# power.net
KiCad netlist of a schematic drawn in EAGLE
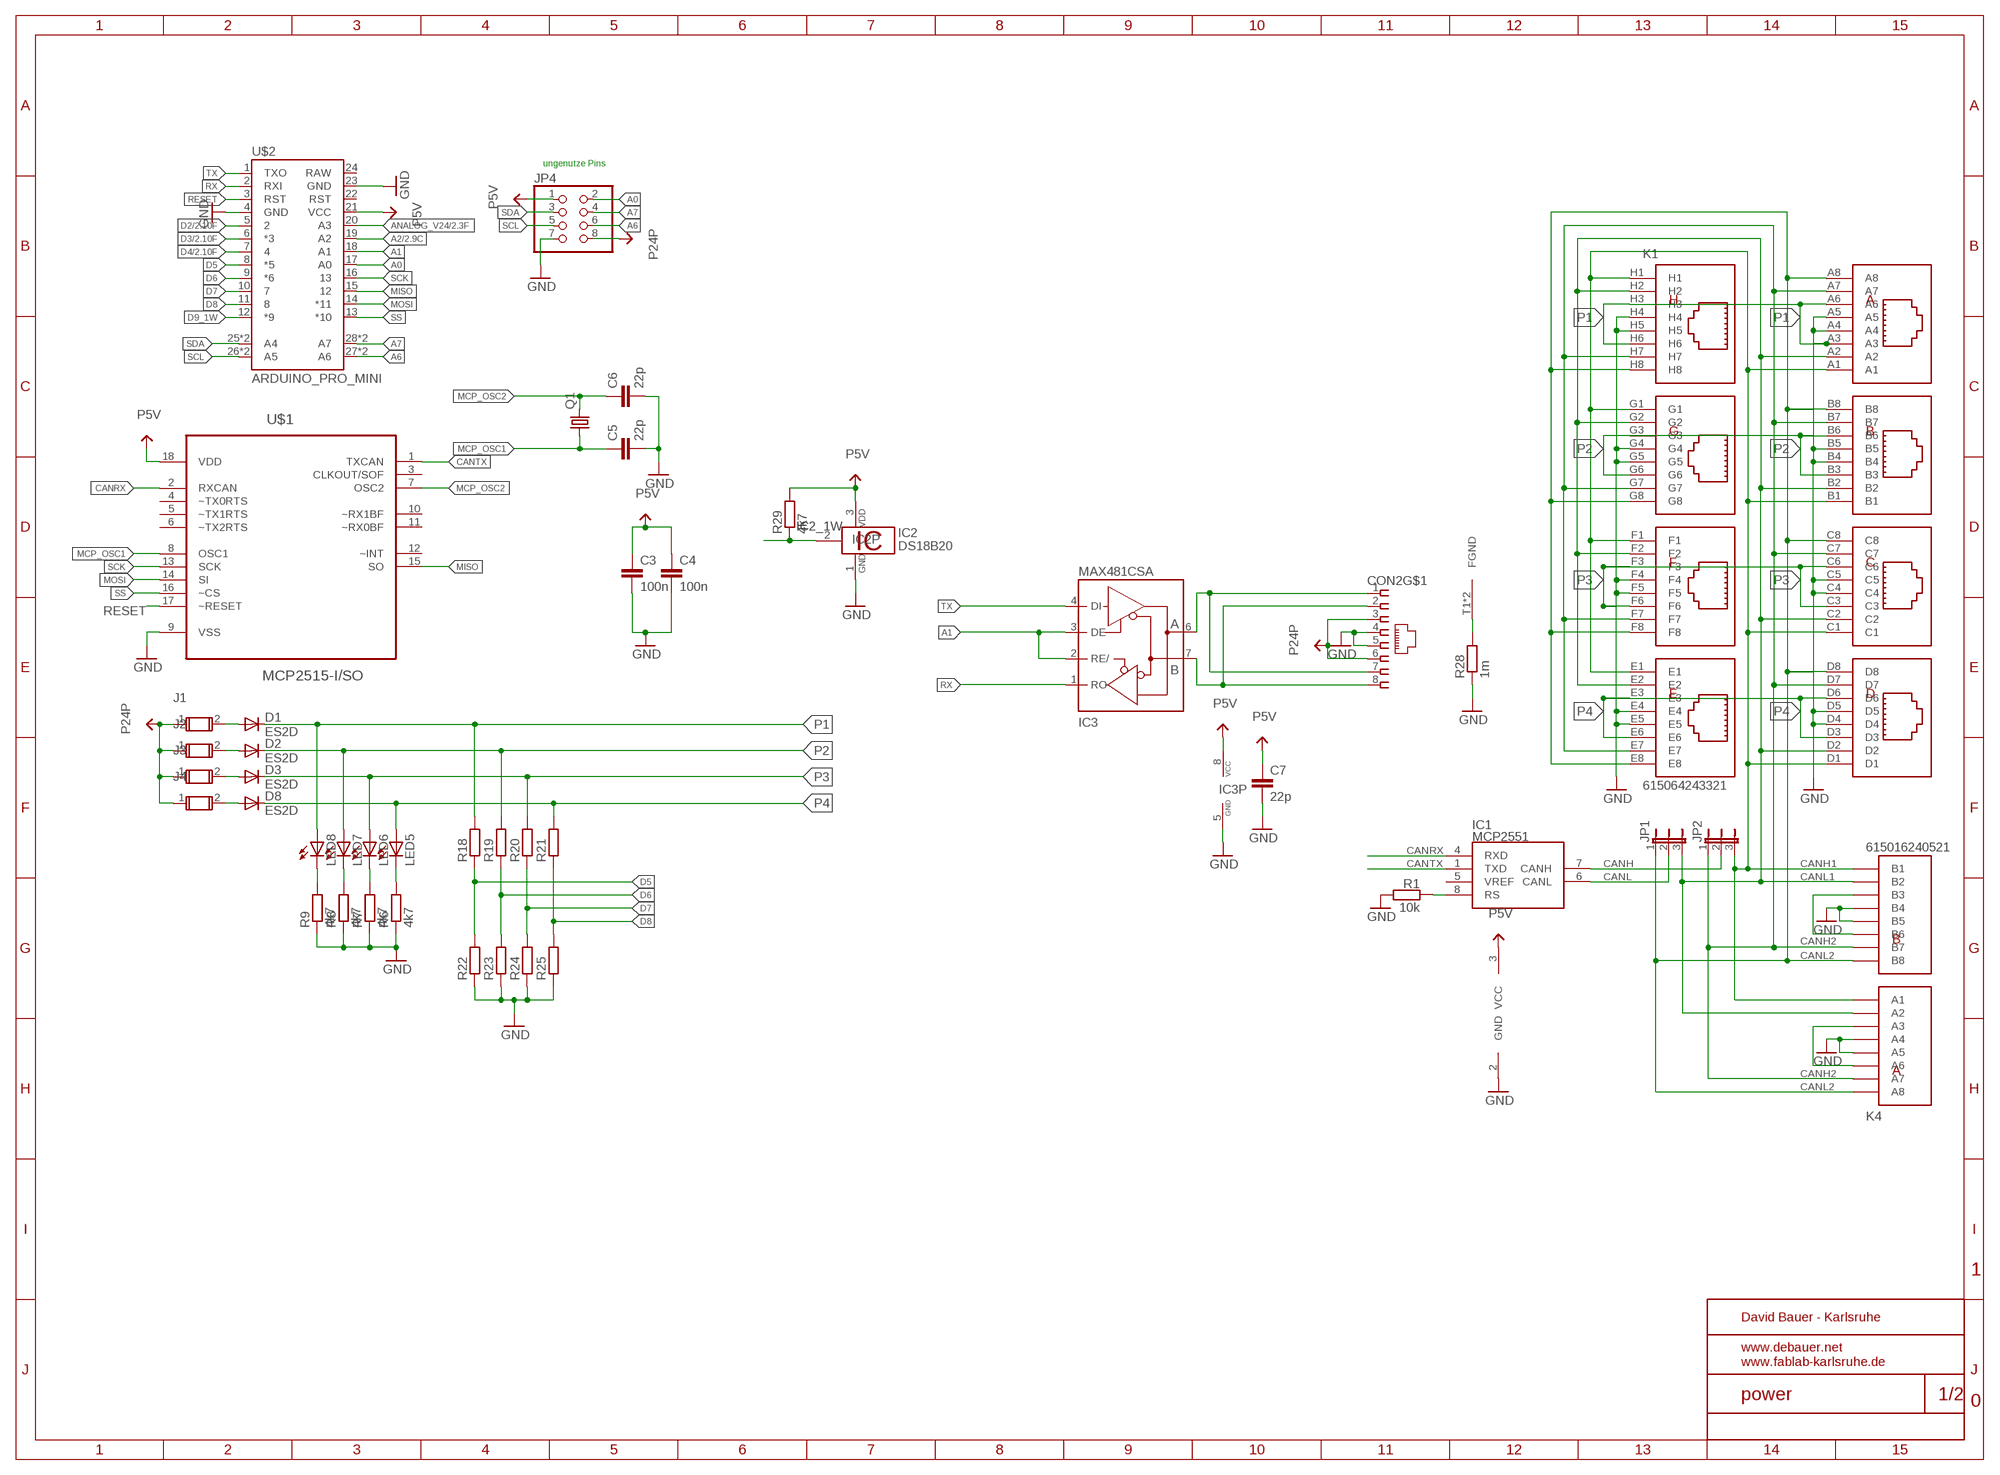
[diagram p0: schematic, sheet 1]
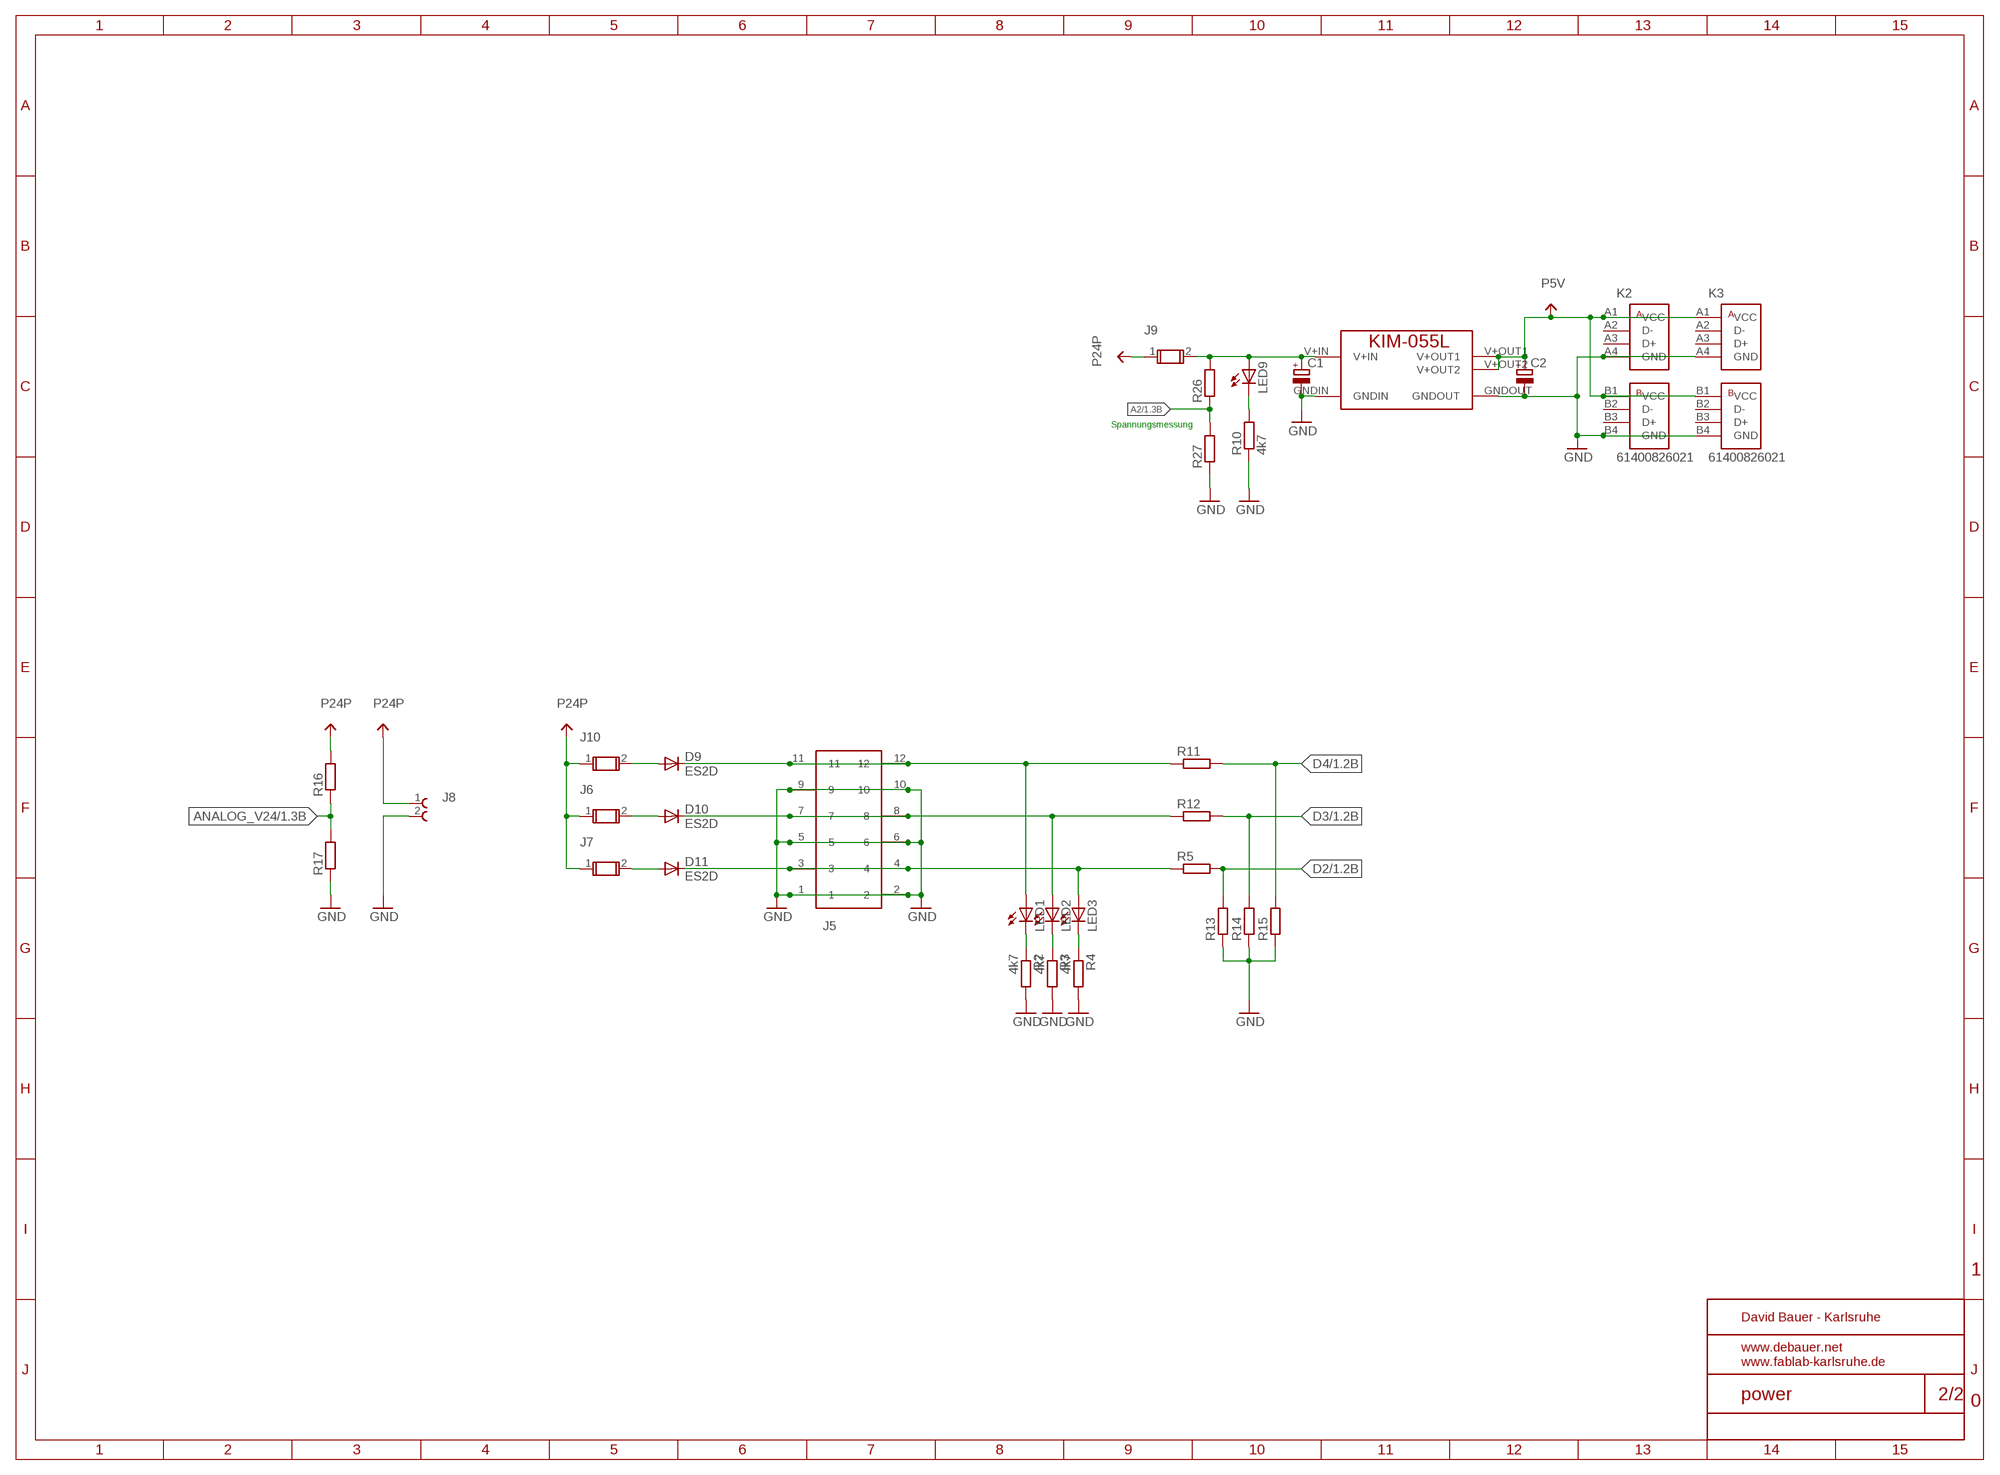
[diagram p1: schematic, sheet 2]

(export (version "E")
  (design (tool "Eeschema 10.0.6"))
  (components
    (comp (ref "C1")
      (value "CPOL-EUE5-10.5")
      (footprint "eagle-import:E5-10,5")
      (libsource (lib "eagle-import") (part "CPOL-EUE5-10.5"))
    )
    (comp (ref "C2")
      (value "CPOL-EUE5-10.5")
      (footprint "eagle-import:E5-10,5")
      (libsource (lib "eagle-import") (part "CPOL-EUE5-10.5"))
    )
    (comp (ref "D9")
      (value "ES2D")
      (footprint "eagle-import:SMB")
      (libsource (lib "eagle-import") (part "ES2D"))
    )
    (comp (ref "D10")
      (value "ES2D")
      (footprint "eagle-import:SMB")
      (libsource (lib "eagle-import") (part "ES2D"))
    )
    (comp (ref "D11")
      (value "ES2D")
      (footprint "eagle-import:SMB")
      (libsource (lib "eagle-import") (part "ES2D"))
    )
    (comp (ref "J5")
      (value "691332510012")
      (footprint "eagle-import:691332510012")
      (libsource (lib "eagle-import") (part "691332510012"))
    )
    (comp (ref "J6")
      (value "696101000002")
      (footprint "eagle-import:696101000002")
      (libsource (lib "eagle-import") (part "696101000002"))
    )
    (comp (ref "J7")
      (value "696101000002")
      (footprint "eagle-import:696101000002")
      (libsource (lib "eagle-import") (part "696101000002"))
    )
    (comp (ref "J8")
      (value "691312510002")
      (footprint "eagle-import:691312510002")
      (libsource (lib "eagle-import") (part "691312510002"))
    )
    (comp (ref "J9")
      (value "696101000002")
      (footprint "eagle-import:696101000002")
      (libsource (lib "eagle-import") (part "696101000002"))
    )
    (comp (ref "J10")
      (value "696101000002")
      (footprint "eagle-import:696101000002")
      (libsource (lib "eagle-import") (part "696101000002"))
    )
    (comp (ref "K2")
      (value "61400826021")
      (footprint "eagle-import:61400826021")
      (libsource (lib "eagle-import") (part "61400826021"))
    )
    (comp (ref "K3")
      (value "61400826021")
      (footprint "eagle-import:61400826021")
      (libsource (lib "eagle-import") (part "61400826021"))
    )
    (comp (ref "LED1")
      (value "LED3MM")
      (footprint "eagle-import:LED3MM")
      (libsource (lib "eagle-import") (part "LED3MM"))
    )
    (comp (ref "LED2")
      (value "LED3MM")
      (footprint "eagle-import:LED3MM")
      (libsource (lib "eagle-import") (part "LED3MM"))
    )
    (comp (ref "LED3")
      (value "LED3MM")
      (footprint "eagle-import:LED3MM")
      (libsource (lib "eagle-import") (part "LED3MM"))
    )
    (comp (ref "LED9")
      (value "LED3MM")
      (footprint "eagle-import:LED3MM")
      (libsource (lib "eagle-import") (part "LED3MM"))
    )
    (comp (ref "MOD1")
      (value "KIM-055L")
      (footprint "eagle-import:KIM-055L")
      (libsource (lib "eagle-import") (part "KIM-055L"))
    )
    (comp (ref "R2")
      (value "4k7")
      (footprint "eagle-import:R0805")
      (libsource (lib "eagle-import") (part "schlager_passiv_R-EU_R0805"))
    )
    (comp (ref "R3")
      (value "4k7")
      (footprint "eagle-import:R0805")
      (libsource (lib "eagle-import") (part "schlager_passiv_R-EU_R0805"))
    )
    (comp (ref "R4")
      (value "4k7")
      (footprint "eagle-import:R0805")
      (libsource (lib "eagle-import") (part "schlager_passiv_R-EU_R0805"))
    )
    (comp (ref "R5")
      (value "R-EU_R0805")
      (footprint "eagle-import:R0805")
      (libsource (lib "eagle-import") (part "schlager_passiv_R-EU_R0805"))
    )
    (comp (ref "R10")
      (value "4k7")
      (footprint "eagle-import:R0805")
      (libsource (lib "eagle-import") (part "schlager_passiv_R-EU_R0805"))
    )
    (comp (ref "R11")
      (value "R-EU_R0805")
      (footprint "eagle-import:R0805")
      (libsource (lib "eagle-import") (part "schlager_passiv_R-EU_R0805"))
    )
    (comp (ref "R12")
      (value "R-EU_R0805")
      (footprint "eagle-import:R0805")
      (libsource (lib "eagle-import") (part "schlager_passiv_R-EU_R0805"))
    )
    (comp (ref "R13")
      (value "R-EU_R0805")
      (footprint "eagle-import:R0805")
      (libsource (lib "eagle-import") (part "schlager_passiv_R-EU_R0805"))
    )
    (comp (ref "R14")
      (value "R-EU_R0805")
      (footprint "eagle-import:R0805")
      (libsource (lib "eagle-import") (part "schlager_passiv_R-EU_R0805"))
    )
    (comp (ref "R15")
      (value "R-EU_R0805")
      (footprint "eagle-import:R0805")
      (libsource (lib "eagle-import") (part "schlager_passiv_R-EU_R0805"))
    )
    (comp (ref "R16")
      (value "R-EU_R0805")
      (footprint "eagle-import:R0805")
      (libsource (lib "eagle-import") (part "schlager_passiv_R-EU_R0805"))
    )
    (comp (ref "R17")
      (value "R-EU_R0805")
      (footprint "eagle-import:R0805")
      (libsource (lib "eagle-import") (part "schlager_passiv_R-EU_R0805"))
    )
    (comp (ref "R26")
      (value "R-EU_R0805")
      (footprint "eagle-import:R0805")
      (libsource (lib "eagle-import") (part "schlager_passiv_R-EU_R0805"))
    )
    (comp (ref "R27")
      (value "R-EU_R0805")
      (footprint "eagle-import:R0805")
      (libsource (lib "eagle-import") (part "schlager_passiv_R-EU_R0805"))
    )
    (comp (ref "C3")
      (value "100n")
      (footprint "eagle-import:C0805")
      (libsource (lib "eagle-import") (part "C-EUC0805"))
    )
    (comp (ref "C4")
      (value "100n")
      (footprint "eagle-import:C0805")
      (libsource (lib "eagle-import") (part "C-EUC0805"))
    )
    (comp (ref "C5")
      (value "22p")
      (footprint "eagle-import:C0805")
      (libsource (lib "eagle-import") (part "C-EUC0805"))
    )
    (comp (ref "C6")
      (value "22p")
      (footprint "eagle-import:C0805")
      (libsource (lib "eagle-import") (part "C-EUC0805"))
    )
    (comp (ref "C7")
      (value "22p")
      (footprint "eagle-import:C0805")
      (libsource (lib "eagle-import") (part "C-EUC0805"))
    )
    (comp (ref "CON2")
      (value "MEBP_8-8G")
      (footprint "eagle-import:MEBP")
      (libsource (lib "eagle-import") (part "MEBP_8-8G"))
    )
    (comp (ref "D1")
      (value "ES2D")
      (footprint "eagle-import:SMB")
      (libsource (lib "eagle-import") (part "ES2D"))
    )
    (comp (ref "D2")
      (value "ES2D")
      (footprint "eagle-import:SMB")
      (libsource (lib "eagle-import") (part "ES2D"))
    )
    (comp (ref "D3")
      (value "ES2D")
      (footprint "eagle-import:SMB")
      (libsource (lib "eagle-import") (part "ES2D"))
    )
    (comp (ref "D8")
      (value "ES2D")
      (footprint "eagle-import:SMB")
      (libsource (lib "eagle-import") (part "ES2D"))
    )
    (comp (ref "IC1")
      (value "MCP2551")
      (footprint "eagle-import:SO-8")
      (libsource (lib "eagle-import") (part "MCP2551"))
    )
    (comp (ref "IC2")
      (value "DS18B20")
      (footprint "eagle-import:TO92-")
      (libsource (lib "eagle-import") (part "DS18B20"))
    )
    (comp (ref "IC3")
      (value "MAX481CSA")
      (footprint "eagle-import:SO08")
      (fields (field (name "MF") "MAXIM"))
      (libsource (lib "eagle-import") (part "MAX481CSA"))
    )
    (comp (ref "J1")
      (value "696101000002")
      (footprint "eagle-import:696101000002")
      (libsource (lib "eagle-import") (part "696101000002"))
    )
    (comp (ref "J2")
      (value "696101000002")
      (footprint "eagle-import:696101000002")
      (libsource (lib "eagle-import") (part "696101000002"))
    )
    (comp (ref "J3")
      (value "696101000002")
      (footprint "eagle-import:696101000002")
      (libsource (lib "eagle-import") (part "696101000002"))
    )
    (comp (ref "J4")
      (value "696101000002")
      (footprint "eagle-import:696101000002")
      (libsource (lib "eagle-import") (part "696101000002"))
    )
    (comp (ref "JP1")
      (value "JP2E")
      (footprint "eagle-import:JP2")
      (libsource (lib "eagle-import") (part "JP2E"))
    )
    (comp (ref "JP2")
      (value "JP2E")
      (footprint "eagle-import:JP2")
      (libsource (lib "eagle-import") (part "JP2E"))
    )
    (comp (ref "JP4")
      (value "PINHD-2X4")
      (footprint "eagle-import:2X04")
      (libsource (lib "eagle-import") (part "PINHD-2X4"))
    )
    (comp (ref "K1")
      (value "615064243321")
      (footprint "eagle-import:615064243321")
      (libsource (lib "eagle-import") (part "615064243321"))
    )
    (comp (ref "K4")
      (value "615016240521")
      (footprint "eagle-import:615016240521")
      (libsource (lib "eagle-import") (part "615016240521"))
    )
    (comp (ref "LED5")
      (value "LED3MM")
      (footprint "eagle-import:LED3MM")
      (libsource (lib "eagle-import") (part "LED3MM"))
    )
    (comp (ref "LED6")
      (value "LED3MM")
      (footprint "eagle-import:LED3MM")
      (libsource (lib "eagle-import") (part "LED3MM"))
    )
    (comp (ref "LED7")
      (value "LED3MM")
      (footprint "eagle-import:LED3MM")
      (libsource (lib "eagle-import") (part "LED3MM"))
    )
    (comp (ref "LED8")
      (value "LED3MM")
      (footprint "eagle-import:LED3MM")
      (libsource (lib "eagle-import") (part "LED3MM"))
    )
    (comp (ref "Q1")
      (value "CRYSTALHC49S")
      (footprint "eagle-import:HC49_S")
      (libsource (lib "eagle-import") (part "CRYSTALHC49S"))
    )
    (comp (ref "R1")
      (value "10k")
      (footprint "eagle-import:R0603")
      (libsource (lib "eagle-import") (part "R-EU_R0603"))
    )
    (comp (ref "R6")
      (value "4k7")
      (footprint "eagle-import:R0805")
      (libsource (lib "eagle-import") (part "schlager_passiv_R-EU_R0805"))
    )
    (comp (ref "R7")
      (value "4k7")
      (footprint "eagle-import:R0805")
      (libsource (lib "eagle-import") (part "schlager_passiv_R-EU_R0805"))
    )
    (comp (ref "R8")
      (value "4k7")
      (footprint "eagle-import:R0805")
      (libsource (lib "eagle-import") (part "schlager_passiv_R-EU_R0805"))
    )
    (comp (ref "R9")
      (value "4k7")
      (footprint "eagle-import:R0805")
      (libsource (lib "eagle-import") (part "schlager_passiv_R-EU_R0805"))
    )
    (comp (ref "R18")
      (value "R-EU_R0805")
      (footprint "eagle-import:R0805")
      (libsource (lib "eagle-import") (part "schlager_passiv_R-EU_R0805"))
    )
    (comp (ref "R19")
      (value "R-EU_R0805")
      (footprint "eagle-import:R0805")
      (libsource (lib "eagle-import") (part "schlager_passiv_R-EU_R0805"))
    )
    (comp (ref "R20")
      (value "R-EU_R0805")
      (footprint "eagle-import:R0805")
      (libsource (lib "eagle-import") (part "schlager_passiv_R-EU_R0805"))
    )
    (comp (ref "R21")
      (value "R-EU_R0805")
      (footprint "eagle-import:R0805")
      (libsource (lib "eagle-import") (part "schlager_passiv_R-EU_R0805"))
    )
    (comp (ref "R22")
      (value "R-EU_R0805")
      (footprint "eagle-import:R0805")
      (libsource (lib "eagle-import") (part "schlager_passiv_R-EU_R0805"))
    )
    (comp (ref "R23")
      (value "R-EU_R0805")
      (footprint "eagle-import:R0805")
      (libsource (lib "eagle-import") (part "schlager_passiv_R-EU_R0805"))
    )
    (comp (ref "R24")
      (value "R-EU_R0805")
      (footprint "eagle-import:R0805")
      (libsource (lib "eagle-import") (part "schlager_passiv_R-EU_R0805"))
    )
    (comp (ref "R25")
      (value "R-EU_R0805")
      (footprint "eagle-import:R0805")
      (libsource (lib "eagle-import") (part "schlager_passiv_R-EU_R0805"))
    )
    (comp (ref "R28")
      (value "1m")
      (footprint "eagle-import:R0805")
      (libsource (lib "eagle-import") (part "schlager_passiv_R-EU_R0805"))
    )
    (comp (ref "R29")
      (value "4k7")
      (footprint "eagle-import:R0805")
      (libsource (lib "eagle-import") (part "schlager_passiv_R-EU_R0805"))
    )
    (comp (ref "U$1")
      (value "MCP2515-I/SO")
      (footprint "eagle-import:SOIC127P1034X264-18N")
      (libsource (lib "eagle-import") (part "MCP2515-I/SO"))
    )
    (comp (ref "U$2")
      (value "ARDUINO_PRO_MINI")
      (footprint "eagle-import:ARDUINO_PRO_MINI")
      (libsource (lib "eagle-import") (part "ARDUINO_PRO_MINI"))
    )
  )
  (nets
    (net (code "1") (name "A0") (class "Default")
      (node (ref "JP4") (pin "2") (pinfunction "2_2") (pintype "passive"))
      (node (ref "U$2") (pin "17") (pinfunction "A0_17") (pintype "bidirectional"))
    )
    (net (code "2") (name "A1") (class "Default")
      (node (ref "IC3") (pin "2") (pinfunction "RE/_2") (pintype "input"))
      (node (ref "IC3") (pin "3") (pinfunction "DE_3") (pintype "input"))
      (node (ref "U$2") (pin "18") (pinfunction "A1_18") (pintype "bidirectional"))
    )
    (net (code "3") (name "A2") (class "Default")
      (node (ref "R26") (pin "1") (pinfunction "1_1") (pintype "passive"))
      (node (ref "R27") (pin "2") (pinfunction "2_2") (pintype "passive"))
      (node (ref "U$2") (pin "19") (pinfunction "A2_19") (pintype "bidirectional"))
    )
    (net (code "4") (name "A6") (class "Default")
      (node (ref "JP4") (pin "6") (pinfunction "6_6") (pintype "passive"))
      (node (ref "U$2") (pin "27") (pinfunction "A6_27") (pintype "bidirectional"))
      (node (ref "U$2") (pin "A6") (pinfunction "A6_A6") (pintype "bidirectional"))
    )
    (net (code "5") (name "A7") (class "Default")
      (node (ref "JP4") (pin "4") (pinfunction "4_4") (pintype "passive"))
      (node (ref "U$2") (pin "28") (pinfunction "A7_28") (pintype "bidirectional"))
      (node (ref "U$2") (pin "A7") (pinfunction "A7_A7") (pintype "bidirectional"))
    )
    (net (code "6") (name "ANALOG_V24") (class "Default")
      (node (ref "R16") (pin "1") (pinfunction "1_1") (pintype "passive"))
      (node (ref "R17") (pin "2") (pinfunction "2_2") (pintype "passive"))
      (node (ref "U$2") (pin "20") (pinfunction "A3_20") (pintype "bidirectional"))
    )
    (net (code "7") (name "CANH") (class "Default")
      (node (ref "IC1") (pin "7") (pinfunction "CANH_7") (pintype "bidirectional"))
      (node (ref "JP2") (pin "2") (pinfunction "2_2") (pintype "passive"))
    )
    (net (code "8") (name "CANH1") (class "Default")
      (node (ref "JP2") (pin "3") (pinfunction "3_3") (pintype "passive"))
      (node (ref "K1") (pin "A1") (pinfunction "A1_A1") (pintype "passive"))
      (node (ref "K1") (pin "B1") (pinfunction "B1_B1") (pintype "passive"))
      (node (ref "K1") (pin "C1") (pinfunction "C1_C1") (pintype "passive"))
      (node (ref "K1") (pin "D1") (pinfunction "D1_D1") (pintype "passive"))
      (node (ref "K1") (pin "E1") (pinfunction "E1_E1") (pintype "passive"))
      (node (ref "K1") (pin "F1") (pinfunction "F1_F1") (pintype "passive"))
      (node (ref "K1") (pin "G1") (pinfunction "G1_G1") (pintype "passive"))
      (node (ref "K1") (pin "H1") (pinfunction "H1_H1") (pintype "passive"))
      (node (ref "K4") (pin "A1") (pinfunction "A1_A1") (pintype "passive"))
      (node (ref "K4") (pin "B1") (pinfunction "B1_B1") (pintype "passive"))
    )
    (net (code "9") (name "CANH2") (class "Default")
      (node (ref "JP2") (pin "1") (pinfunction "1_1") (pintype "passive"))
      (node (ref "K1") (pin "A7") (pinfunction "A7_A7") (pintype "passive"))
      (node (ref "K1") (pin "B7") (pinfunction "B7_B7") (pintype "passive"))
      (node (ref "K1") (pin "C7") (pinfunction "C7_C7") (pintype "passive"))
      (node (ref "K1") (pin "D7") (pinfunction "D7_D7") (pintype "passive"))
      (node (ref "K1") (pin "E7") (pinfunction "E7_E7") (pintype "passive"))
      (node (ref "K1") (pin "F7") (pinfunction "F7_F7") (pintype "passive"))
      (node (ref "K1") (pin "G7") (pinfunction "G7_G7") (pintype "passive"))
      (node (ref "K1") (pin "H7") (pinfunction "H7_H7") (pintype "passive"))
      (node (ref "K4") (pin "A7") (pinfunction "A7_A7") (pintype "passive"))
      (node (ref "K4") (pin "B7") (pinfunction "B7_B7") (pintype "passive"))
    )
    (net (code "10") (name "CANL") (class "Default")
      (node (ref "IC1") (pin "6") (pinfunction "CANL_6") (pintype "bidirectional"))
      (node (ref "JP1") (pin "2") (pinfunction "2_2") (pintype "passive"))
    )
    (net (code "11") (name "CANL1") (class "Default")
      (node (ref "JP1") (pin "3") (pinfunction "3_3") (pintype "passive"))
      (node (ref "K1") (pin "A2") (pinfunction "A2_A2") (pintype "passive"))
      (node (ref "K1") (pin "B2") (pinfunction "B2_B2") (pintype "passive"))
      (node (ref "K1") (pin "C2") (pinfunction "C2_C2") (pintype "passive"))
      (node (ref "K1") (pin "D2") (pinfunction "D2_D2") (pintype "passive"))
      (node (ref "K1") (pin "E2") (pinfunction "E2_E2") (pintype "passive"))
      (node (ref "K1") (pin "F2") (pinfunction "F2_F2") (pintype "passive"))
      (node (ref "K1") (pin "G2") (pinfunction "G2_G2") (pintype "passive"))
      (node (ref "K1") (pin "H2") (pinfunction "H2_H2") (pintype "passive"))
      (node (ref "K4") (pin "A2") (pinfunction "A2_A2") (pintype "passive"))
      (node (ref "K4") (pin "B2") (pinfunction "B2_B2") (pintype "passive"))
    )
    (net (code "12") (name "CANL2") (class "Default")
      (node (ref "JP1") (pin "1") (pinfunction "1_1") (pintype "passive"))
      (node (ref "K1") (pin "A8") (pinfunction "A8_A8") (pintype "passive"))
      (node (ref "K1") (pin "B8") (pinfunction "B8_B8") (pintype "passive"))
      (node (ref "K1") (pin "C8") (pinfunction "C8_C8") (pintype "passive"))
      (node (ref "K1") (pin "D8") (pinfunction "D8_D8") (pintype "passive"))
      (node (ref "K1") (pin "E8") (pinfunction "E8_E8") (pintype "passive"))
      (node (ref "K1") (pin "F8") (pinfunction "F8_F8") (pintype "passive"))
      (node (ref "K1") (pin "G8") (pinfunction "G8_G8") (pintype "passive"))
      (node (ref "K1") (pin "H8") (pinfunction "H8_H8") (pintype "passive"))
      (node (ref "K4") (pin "A8") (pinfunction "A8_A8") (pintype "passive"))
      (node (ref "K4") (pin "B8") (pinfunction "B8_B8") (pintype "passive"))
    )
    (net (code "13") (name "CANRX") (class "Default")
      (node (ref "IC1") (pin "4") (pinfunction "RXD_4") (pintype "bidirectional"))
      (node (ref "U$1") (pin "2") (pinfunction "RXCAN_2") (pintype "input"))
    )
    (net (code "14") (name "CANTX") (class "Default")
      (node (ref "IC1") (pin "1") (pinfunction "TXD_1") (pintype "bidirectional"))
      (node (ref "U$1") (pin "1") (pinfunction "TXCAN_1") (pintype "output"))
    )
    (net (code "15") (name "D2") (class "Default")
      (node (ref "R13") (pin "2") (pinfunction "2_2") (pintype "passive"))
      (node (ref "R5") (pin "2") (pinfunction "2_2") (pintype "passive"))
      (node (ref "U$2") (pin "5") (pinfunction "2_5") (pintype "bidirectional"))
    )
    (net (code "16") (name "D3") (class "Default")
      (node (ref "R12") (pin "2") (pinfunction "2_2") (pintype "passive"))
      (node (ref "R14") (pin "2") (pinfunction "2_2") (pintype "passive"))
      (node (ref "U$2") (pin "6") (pinfunction "*3_6") (pintype "bidirectional"))
    )
    (net (code "17") (name "D4") (class "Default")
      (node (ref "R11") (pin "2") (pinfunction "2_2") (pintype "passive"))
      (node (ref "R15") (pin "2") (pinfunction "2_2") (pintype "passive"))
      (node (ref "U$2") (pin "7") (pinfunction "4_7") (pintype "bidirectional"))
    )
    (net (code "18") (name "D5") (class "Default")
      (node (ref "R18") (pin "1") (pinfunction "1_1") (pintype "passive"))
      (node (ref "R22") (pin "2") (pinfunction "2_2") (pintype "passive"))
      (node (ref "U$2") (pin "8") (pinfunction "*5_8") (pintype "bidirectional"))
    )
    (net (code "19") (name "D6") (class "Default")
      (node (ref "R19") (pin "1") (pinfunction "1_1") (pintype "passive"))
      (node (ref "R23") (pin "2") (pinfunction "2_2") (pintype "passive"))
      (node (ref "U$2") (pin "9") (pinfunction "*6_9") (pintype "bidirectional"))
    )
    (net (code "20") (name "D7") (class "Default")
      (node (ref "R20") (pin "1") (pinfunction "1_1") (pintype "passive"))
      (node (ref "R24") (pin "2") (pinfunction "2_2") (pintype "passive"))
      (node (ref "U$2") (pin "10") (pinfunction "7_10") (pintype "bidirectional"))
    )
    (net (code "21") (name "D8") (class "Default")
      (node (ref "R21") (pin "1") (pinfunction "1_1") (pintype "passive"))
      (node (ref "R25") (pin "2") (pinfunction "2_2") (pintype "passive"))
      (node (ref "U$2") (pin "11") (pinfunction "8_11") (pintype "bidirectional"))
    )
    (net (code "22") (name "D9_1W") (class "Default")
      (node (ref "IC2") (pin "2") (pinfunction "1W_2") (pintype "power_in"))
      (node (ref "R29") (pin "1") (pinfunction "1_1") (pintype "passive"))
      (node (ref "U$2") (pin "12") (pinfunction "*9_12") (pintype "bidirectional"))
    )
    (net (code "23") (name "GND") (class "Default")
      (node (ref "C1") (pin "-") (pinfunction "-_-") (pintype "passive"))
      (node (ref "C2") (pin "-") (pinfunction "-_-") (pintype "passive"))
      (node (ref "C3") (pin "2") (pinfunction "2_2") (pintype "passive"))
      (node (ref "C4") (pin "2") (pinfunction "2_2") (pintype "passive"))
      (node (ref "C5") (pin "2") (pinfunction "2_2") (pintype "passive"))
      (node (ref "C6") (pin "2") (pinfunction "2_2") (pintype "passive"))
      (node (ref "C7") (pin "2") (pinfunction "2_2") (pintype "passive"))
      (node (ref "CON2") (pin "4") (pinfunction "4_4") (pintype "passive"))
      (node (ref "CON2") (pin "5") (pinfunction "5_5") (pintype "passive"))
      (node (ref "IC1") (pin "2") (pinfunction "GND_2") (pintype "power_in"))
      (node (ref "IC2") (pin "1") (pinfunction "GND_1") (pintype "power_in"))
      (node (ref "IC3") (pin "5") (pinfunction "GND_5") (pintype "power_in"))
      (node (ref "J5") (pin "1") (pinfunction "1_1") (pintype "passive"))
      (node (ref "J5") (pin "10") (pinfunction "10_10") (pintype "passive"))
      (node (ref "J5") (pin "2") (pinfunction "2_2") (pintype "passive"))
      (node (ref "J5") (pin "5") (pinfunction "5_5") (pintype "passive"))
      (node (ref "J5") (pin "6") (pinfunction "6_6") (pintype "passive"))
      (node (ref "J5") (pin "9") (pinfunction "9_9") (pintype "passive"))
      (node (ref "J8") (pin "2") (pinfunction "2_2") (pintype "passive"))
      (node (ref "JP4") (pin "7") (pinfunction "7_7") (pintype "passive"))
      (node (ref "K1") (pin "A4") (pinfunction "A4_A4") (pintype "passive"))
      (node (ref "K1") (pin "A5") (pinfunction "A5_A5") (pintype "passive"))
      (node (ref "K1") (pin "B4") (pinfunction "B4_B4") (pintype "passive"))
      (node (ref "K1") (pin "B5") (pinfunction "B5_B5") (pintype "passive"))
      (node (ref "K1") (pin "C4") (pinfunction "C4_C4") (pintype "passive"))
      (node (ref "K1") (pin "C5") (pinfunction "C5_C5") (pintype "passive"))
      (node (ref "K1") (pin "D4") (pinfunction "D4_D4") (pintype "passive"))
      (node (ref "K1") (pin "D5") (pinfunction "D5_D5") (pintype "passive"))
      (node (ref "K1") (pin "E4") (pinfunction "E4_E4") (pintype "passive"))
      (node (ref "K1") (pin "E5") (pinfunction "E5_E5") (pintype "passive"))
      (node (ref "K1") (pin "F4") (pinfunction "F4_F4") (pintype "passive"))
      (node (ref "K1") (pin "F5") (pinfunction "F5_F5") (pintype "passive"))
      (node (ref "K1") (pin "G4") (pinfunction "G4_G4") (pintype "passive"))
      (node (ref "K1") (pin "G5") (pinfunction "G5_G5") (pintype "passive"))
      (node (ref "K1") (pin "H4") (pinfunction "H4_H4") (pintype "passive"))
      (node (ref "K1") (pin "H5") (pinfunction "H5_H5") (pintype "passive"))
      (node (ref "K2") (pin "A4") (pinfunction "GND_A4") (pintype "bidirectional"))
      (node (ref "K2") (pin "B4") (pinfunction "GND_B4") (pintype "bidirectional"))
      (node (ref "K3") (pin "A4") (pinfunction "GND_A4") (pintype "bidirectional"))
      (node (ref "K3") (pin "B4") (pinfunction "GND_B4") (pintype "bidirectional"))
      (node (ref "K4") (pin "A4") (pinfunction "A4_A4") (pintype "passive"))
      (node (ref "K4") (pin "A5") (pinfunction "A5_A5") (pintype "passive"))
      (node (ref "K4") (pin "B4") (pinfunction "B4_B4") (pintype "passive"))
      (node (ref "K4") (pin "B5") (pinfunction "B5_B5") (pintype "passive"))
      (node (ref "MOD1") (pin "GNDIN") (pinfunction "GNDIN_GNDIN") (pintype "bidirectional"))
      (node (ref "MOD1") (pin "GNDOUT") (pinfunction "GNDOUT_GNDOUT") (pintype "bidirectional"))
      (node (ref "R1") (pin "2") (pinfunction "2_2") (pintype "passive"))
      (node (ref "R10") (pin "1") (pinfunction "1_1") (pintype "passive"))
      (node (ref "R13") (pin "1") (pinfunction "1_1") (pintype "passive"))
      (node (ref "R14") (pin "1") (pinfunction "1_1") (pintype "passive"))
      (node (ref "R15") (pin "1") (pinfunction "1_1") (pintype "passive"))
      (node (ref "R17") (pin "1") (pinfunction "1_1") (pintype "passive"))
      (node (ref "R2") (pin "2") (pinfunction "2_2") (pintype "passive"))
      (node (ref "R22") (pin "1") (pinfunction "1_1") (pintype "passive"))
      (node (ref "R23") (pin "1") (pinfunction "1_1") (pintype "passive"))
      (node (ref "R24") (pin "1") (pinfunction "1_1") (pintype "passive"))
      (node (ref "R25") (pin "1") (pinfunction "1_1") (pintype "passive"))
      (node (ref "R27") (pin "1") (pinfunction "1_1") (pintype "passive"))
      (node (ref "R28") (pin "1") (pinfunction "1_1") (pintype "passive"))
      (node (ref "R3") (pin "2") (pinfunction "2_2") (pintype "passive"))
      (node (ref "R4") (pin "2") (pinfunction "2_2") (pintype "passive"))
      (node (ref "R6") (pin "1") (pinfunction "1_1") (pintype "passive"))
      (node (ref "R7") (pin "1") (pinfunction "1_1") (pintype "passive"))
      (node (ref "R8") (pin "1") (pinfunction "1_1") (pintype "passive"))
      (node (ref "R9") (pin "1") (pinfunction "1_1") (pintype "passive"))
      (node (ref "U$1") (pin "9") (pinfunction "VSS_9") (pintype "power_in"))
      (node (ref "U$2") (pin "23") (pinfunction "GND_23") (pintype "bidirectional"))
      (node (ref "U$2") (pin "4") (pinfunction "GND_4") (pintype "bidirectional"))
    )
    (net (code "24") (name "MCP_OSC1") (class "Default")
      (node (ref "C5") (pin "1") (pinfunction "1_1") (pintype "passive"))
      (node (ref "Q1") (pin "1") (pinfunction "1_1") (pintype "passive"))
      (node (ref "U$1") (pin "8") (pinfunction "OSC1_8") (pintype "input"))
    )
    (net (code "25") (name "MCP_OSC2") (class "Default")
      (node (ref "C6") (pin "1") (pinfunction "1_1") (pintype "passive"))
      (node (ref "Q1") (pin "2") (pinfunction "2_2") (pintype "passive"))
      (node (ref "U$1") (pin "7") (pinfunction "OSC2_7") (pintype "output"))
    )
    (net (code "26") (name "MISO") (class "Default")
      (node (ref "U$1") (pin "15") (pinfunction "SO_15") (pintype "output"))
      (node (ref "U$2") (pin "15") (pinfunction "12_15") (pintype "bidirectional"))
    )
    (net (code "27") (name "MOSI") (class "Default")
      (node (ref "U$1") (pin "14") (pinfunction "SI_14") (pintype "input"))
      (node (ref "U$2") (pin "14") (pinfunction "*11_14") (pintype "bidirectional"))
    )
    (net (code "28") (name "Net-(C1-Pad+)") (class "Default")
      (node (ref "C1") (pin "+") (pinfunction "+_+") (pintype "passive"))
      (node (ref "J9") (pin "2") (pinfunction "2_2") (pintype "passive"))
      (node (ref "LED9") (pin "A") (pinfunction "A_A") (pintype "passive"))
      (node (ref "MOD1") (pin "V+IN") (pinfunction "V+IN_V+IN") (pintype "bidirectional"))
      (node (ref "R26") (pin "2") (pinfunction "2_2") (pintype "passive"))
    )
    (net (code "29") (name "Net-(CON2B-FGND-PadT1)") (class "Default")
      (node (ref "CON2") (pin "T1") (pinfunction "FGND_T1") (pintype "power_in"))
      (node (ref "CON2") (pin "T2") (pinfunction "FGND_T2") (pintype "power_in"))
      (node (ref "R28") (pin "2") (pinfunction "2_2") (pintype "passive"))
    )
    (net (code "30") (name "Net-(D1-PadA)") (class "Default")
      (node (ref "D1") (pin "A") (pinfunction "A_A") (pintype "passive"))
      (node (ref "J1") (pin "2") (pinfunction "2_2") (pintype "passive"))
    )
    (net (code "31") (name "Net-(D2-PadA)") (class "Default")
      (node (ref "D2") (pin "A") (pinfunction "A_A") (pintype "passive"))
      (node (ref "J2") (pin "2") (pinfunction "2_2") (pintype "passive"))
    )
    (net (code "32") (name "Net-(D3-PadA)") (class "Default")
      (node (ref "D3") (pin "A") (pinfunction "A_A") (pintype "passive"))
      (node (ref "J3") (pin "2") (pinfunction "2_2") (pintype "passive"))
    )
    (net (code "33") (name "Net-(D8-PadA)") (class "Default")
      (node (ref "D8") (pin "A") (pinfunction "A_A") (pintype "passive"))
      (node (ref "J4") (pin "2") (pinfunction "2_2") (pintype "passive"))
    )
    (net (code "34") (name "Net-(D9-PadA)") (class "Default")
      (node (ref "D9") (pin "A") (pinfunction "A_A") (pintype "passive"))
      (node (ref "J10") (pin "2") (pinfunction "2_2") (pintype "passive"))
    )
    (net (code "35") (name "Net-(D9-PadC)") (class "Default")
      (node (ref "D9") (pin "C") (pinfunction "C_C") (pintype "passive"))
      (node (ref "J5") (pin "11") (pinfunction "11_11") (pintype "passive"))
      (node (ref "J5") (pin "12") (pinfunction "12_12") (pintype "passive"))
      (node (ref "LED1") (pin "A") (pinfunction "A_A") (pintype "passive"))
      (node (ref "R11") (pin "1") (pinfunction "1_1") (pintype "passive"))
    )
    (net (code "36") (name "Net-(D10-PadA)") (class "Default")
      (node (ref "D10") (pin "A") (pinfunction "A_A") (pintype "passive"))
      (node (ref "J6") (pin "2") (pinfunction "2_2") (pintype "passive"))
    )
    (net (code "37") (name "Net-(D10-PadC)") (class "Default")
      (node (ref "D10") (pin "C") (pinfunction "C_C") (pintype "passive"))
      (node (ref "J5") (pin "7") (pinfunction "7_7") (pintype "passive"))
      (node (ref "J5") (pin "8") (pinfunction "8_8") (pintype "passive"))
      (node (ref "LED2") (pin "A") (pinfunction "A_A") (pintype "passive"))
      (node (ref "R12") (pin "1") (pinfunction "1_1") (pintype "passive"))
    )
    (net (code "38") (name "Net-(D11-PadA)") (class "Default")
      (node (ref "D11") (pin "A") (pinfunction "A_A") (pintype "passive"))
      (node (ref "J7") (pin "2") (pinfunction "2_2") (pintype "passive"))
    )
    (net (code "39") (name "Net-(D11-PadC)") (class "Default")
      (node (ref "D11") (pin "C") (pinfunction "C_C") (pintype "passive"))
      (node (ref "J5") (pin "3") (pinfunction "3_3") (pintype "passive"))
      (node (ref "J5") (pin "4") (pinfunction "4_4") (pintype "passive"))
      (node (ref "LED3") (pin "A") (pinfunction "A_A") (pintype "passive"))
      (node (ref "R5") (pin "1") (pinfunction "1_1") (pintype "passive"))
    )
    (net (code "40") (name "Net-(IC1A-RS)") (class "Default")
      (node (ref "IC1") (pin "8") (pinfunction "RS_8") (pintype "bidirectional"))
      (node (ref "R1") (pin "1") (pinfunction "1_1") (pintype "passive"))
    )
    (net (code "41") (name "Net-(IC3A-A)") (class "Default")
      (node (ref "CON2") (pin "1") (pinfunction "1_1") (pintype "passive"))
      (node (ref "CON2") (pin "7") (pinfunction "7_7") (pintype "passive"))
      (node (ref "IC3") (pin "6") (pinfunction "A_6") (pintype "passive"))
    )
    (net (code "42") (name "Net-(IC3A-B)") (class "Default")
      (node (ref "CON2") (pin "2") (pinfunction "2_2") (pintype "passive"))
      (node (ref "CON2") (pin "8") (pinfunction "8_8") (pintype "passive"))
      (node (ref "IC3") (pin "7") (pinfunction "B_7") (pintype "passive"))
    )
    (net (code "43") (name "Net-(K4-PadA3)") (class "Default")
      (node (ref "K4") (pin "A3") (pinfunction "A3_A3") (pintype "passive"))
      (node (ref "K4") (pin "A6") (pinfunction "A6_A6") (pintype "passive"))
    )
    (net (code "44") (name "Net-(K4-PadB3)") (class "Default")
      (node (ref "K4") (pin "B3") (pinfunction "B3_B3") (pintype "passive"))
      (node (ref "K4") (pin "B6") (pinfunction "B6_B6") (pintype "passive"))
    )
    (net (code "45") (name "Net-(LED1-C)") (class "Default")
      (node (ref "LED1") (pin "K") (pinfunction "C_K") (pintype "passive"))
      (node (ref "R2") (pin "1") (pinfunction "1_1") (pintype "passive"))
    )
    (net (code "46") (name "Net-(LED2-C)") (class "Default")
      (node (ref "LED2") (pin "K") (pinfunction "C_K") (pintype "passive"))
      (node (ref "R3") (pin "1") (pinfunction "1_1") (pintype "passive"))
    )
    (net (code "47") (name "Net-(LED3-C)") (class "Default")
      (node (ref "LED3") (pin "K") (pinfunction "C_K") (pintype "passive"))
      (node (ref "R4") (pin "1") (pinfunction "1_1") (pintype "passive"))
    )
    (net (code "48") (name "Net-(LED5-C)") (class "Default")
      (node (ref "LED5") (pin "K") (pinfunction "C_K") (pintype "passive"))
      (node (ref "R6") (pin "2") (pinfunction "2_2") (pintype "passive"))
    )
    (net (code "49") (name "Net-(LED6-C)") (class "Default")
      (node (ref "LED6") (pin "K") (pinfunction "C_K") (pintype "passive"))
      (node (ref "R7") (pin "2") (pinfunction "2_2") (pintype "passive"))
    )
    (net (code "50") (name "Net-(LED7-C)") (class "Default")
      (node (ref "LED7") (pin "K") (pinfunction "C_K") (pintype "passive"))
      (node (ref "R8") (pin "2") (pinfunction "2_2") (pintype "passive"))
    )
    (net (code "51") (name "Net-(LED8-C)") (class "Default")
      (node (ref "LED8") (pin "K") (pinfunction "C_K") (pintype "passive"))
      (node (ref "R9") (pin "2") (pinfunction "2_2") (pintype "passive"))
    )
    (net (code "52") (name "Net-(LED9-C)") (class "Default")
      (node (ref "LED9") (pin "K") (pinfunction "C_K") (pintype "passive"))
      (node (ref "R10") (pin "2") (pinfunction "2_2") (pintype "passive"))
    )
    (net (code "53") (name "P1") (class "Default")
      (node (ref "D1") (pin "C") (pinfunction "C_C") (pintype "passive"))
      (node (ref "K1") (pin "A3") (pinfunction "A3_A3") (pintype "passive"))
      (node (ref "K1") (pin "A6") (pinfunction "A6_A6") (pintype "passive"))
      (node (ref "K1") (pin "H3") (pinfunction "H3_H3") (pintype "passive"))
      (node (ref "K1") (pin "H6") (pinfunction "H6_H6") (pintype "passive"))
      (node (ref "LED8") (pin "A") (pinfunction "A_A") (pintype "passive"))
      (node (ref "R18") (pin "2") (pinfunction "2_2") (pintype "passive"))
    )
    (net (code "54") (name "P2") (class "Default")
      (node (ref "D2") (pin "C") (pinfunction "C_C") (pintype "passive"))
      (node (ref "K1") (pin "B3") (pinfunction "B3_B3") (pintype "passive"))
      (node (ref "K1") (pin "B6") (pinfunction "B6_B6") (pintype "passive"))
      (node (ref "K1") (pin "G3") (pinfunction "G3_G3") (pintype "passive"))
      (node (ref "K1") (pin "G6") (pinfunction "G6_G6") (pintype "passive"))
      (node (ref "LED7") (pin "A") (pinfunction "A_A") (pintype "passive"))
      (node (ref "R19") (pin "2") (pinfunction "2_2") (pintype "passive"))
    )
    (net (code "55") (name "P3") (class "Default")
      (node (ref "D3") (pin "C") (pinfunction "C_C") (pintype "passive"))
      (node (ref "K1") (pin "C3") (pinfunction "C3_C3") (pintype "passive"))
      (node (ref "K1") (pin "C6") (pinfunction "C6_C6") (pintype "passive"))
      (node (ref "K1") (pin "F3") (pinfunction "F3_F3") (pintype "passive"))
      (node (ref "K1") (pin "F6") (pinfunction "F6_F6") (pintype "passive"))
      (node (ref "LED6") (pin "A") (pinfunction "A_A") (pintype "passive"))
      (node (ref "R20") (pin "2") (pinfunction "2_2") (pintype "passive"))
    )
    (net (code "56") (name "P4") (class "Default")
      (node (ref "D8") (pin "C") (pinfunction "C_C") (pintype "passive"))
      (node (ref "K1") (pin "D3") (pinfunction "D3_D3") (pintype "passive"))
      (node (ref "K1") (pin "D6") (pinfunction "D6_D6") (pintype "passive"))
      (node (ref "K1") (pin "E3") (pinfunction "E3_E3") (pintype "passive"))
      (node (ref "K1") (pin "E6") (pinfunction "E6_E6") (pintype "passive"))
      (node (ref "LED5") (pin "A") (pinfunction "A_A") (pintype "passive"))
      (node (ref "R21") (pin "2") (pinfunction "2_2") (pintype "passive"))
    )
    (net (code "57") (name "P5V") (class "Default")
      (node (ref "C2") (pin "+") (pinfunction "+_+") (pintype "passive"))
      (node (ref "C3") (pin "1") (pinfunction "1_1") (pintype "passive"))
      (node (ref "C4") (pin "1") (pinfunction "1_1") (pintype "passive"))
      (node (ref "C7") (pin "1") (pinfunction "1_1") (pintype "passive"))
      (node (ref "IC1") (pin "3") (pinfunction "VCC_3") (pintype "power_in"))
      (node (ref "IC2") (pin "3") (pinfunction "VDD_3") (pintype "power_in"))
      (node (ref "IC3") (pin "8") (pinfunction "VCC_8") (pintype "power_in"))
      (node (ref "JP4") (pin "1") (pinfunction "1_1") (pintype "passive"))
      (node (ref "K2") (pin "A1") (pinfunction "VCC_A1") (pintype "bidirectional"))
      (node (ref "K2") (pin "B1") (pinfunction "VCC_B1") (pintype "bidirectional"))
      (node (ref "K3") (pin "A1") (pinfunction "VCC_A1") (pintype "bidirectional"))
      (node (ref "K3") (pin "B1") (pinfunction "VCC_B1") (pintype "bidirectional"))
      (node (ref "MOD1") (pin "V+OUT1") (pinfunction "V+OUT1_V+OUT1") (pintype "bidirectional"))
      (node (ref "MOD1") (pin "V+OUT2") (pinfunction "V+OUT2_V+OUT2") (pintype "bidirectional"))
      (node (ref "R29") (pin "2") (pinfunction "2_2") (pintype "passive"))
      (node (ref "U$1") (pin "18") (pinfunction "VDD_18") (pintype "power_in"))
      (node (ref "U$2") (pin "21") (pinfunction "VCC_21") (pintype "bidirectional"))
    )
    (net (code "58") (name "P24P") (class "Default")
      (node (ref "CON2") (pin "3") (pinfunction "3_3") (pintype "passive"))
      (node (ref "CON2") (pin "6") (pinfunction "6_6") (pintype "passive"))
      (node (ref "J1") (pin "1") (pinfunction "1_1") (pintype "passive"))
      (node (ref "J10") (pin "1") (pinfunction "1_1") (pintype "passive"))
      (node (ref "J2") (pin "1") (pinfunction "1_1") (pintype "passive"))
      (node (ref "J3") (pin "1") (pinfunction "1_1") (pintype "passive"))
      (node (ref "J4") (pin "1") (pinfunction "1_1") (pintype "passive"))
      (node (ref "J6") (pin "1") (pinfunction "1_1") (pintype "passive"))
      (node (ref "J7") (pin "1") (pinfunction "1_1") (pintype "passive"))
      (node (ref "J8") (pin "1") (pinfunction "1_1") (pintype "passive"))
      (node (ref "J9") (pin "1") (pinfunction "1_1") (pintype "passive"))
      (node (ref "JP4") (pin "8") (pinfunction "8_8") (pintype "passive"))
      (node (ref "R16") (pin "2") (pinfunction "2_2") (pintype "passive"))
    )
    (net (code "59") (name "RESET") (class "Default")
      (node (ref "U$1") (pin "17") (pinfunction "~{RESET}_17") (pintype "input"))
      (node (ref "U$2") (pin "3") (pinfunction "RST_3") (pintype "bidirectional"))
    )
    (net (code "60") (name "RX") (class "Default")
      (node (ref "IC3") (pin "1") (pinfunction "RO_1") (pintype "output"))
      (node (ref "U$2") (pin "2") (pinfunction "RXI_2") (pintype "bidirectional"))
    )
    (net (code "61") (name "SCK") (class "Default")
      (node (ref "U$1") (pin "13") (pinfunction "SCK_13") (pintype "input"))
      (node (ref "U$2") (pin "16") (pinfunction "13_16") (pintype "bidirectional"))
    )
    (net (code "62") (name "SCL") (class "Default")
      (node (ref "JP4") (pin "5") (pinfunction "5_5") (pintype "passive"))
      (node (ref "U$2") (pin "26") (pinfunction "A5_26") (pintype "bidirectional"))
      (node (ref "U$2") (pin "A5") (pinfunction "A5_A5") (pintype "bidirectional"))
    )
    (net (code "63") (name "SDA") (class "Default")
      (node (ref "JP4") (pin "3") (pinfunction "3_3") (pintype "passive"))
      (node (ref "U$2") (pin "25") (pinfunction "A4_25") (pintype "bidirectional"))
      (node (ref "U$2") (pin "A4") (pinfunction "A4_A4") (pintype "bidirectional"))
    )
    (net (code "64") (name "SS") (class "Default")
      (node (ref "U$1") (pin "16") (pinfunction "~{CS}_16") (pintype "input"))
      (node (ref "U$2") (pin "13") (pinfunction "*10_13") (pintype "bidirectional"))
    )
    (net (code "65") (name "TX") (class "Default")
      (node (ref "IC3") (pin "4") (pinfunction "DI_4") (pintype "input"))
      (node (ref "U$2") (pin "1") (pinfunction "TXO_1") (pintype "bidirectional"))
    )
    (net (code "66") (name "unconnected-(IC1A-VREF-Pad5)") (class "Default")
      (node (ref "IC1") (pin "5") (pinfunction "VREF_5") (pintype "bidirectional"))
    )
    (net (code "67") (name "unconnected-(K2-D+-PadA3)") (class "Default")
      (node (ref "K2") (pin "A3") (pinfunction "D+_A3") (pintype "bidirectional"))
    )
    (net (code "68") (name "unconnected-(K2-D+-PadB3)") (class "Default")
      (node (ref "K2") (pin "B3") (pinfunction "D+_B3") (pintype "bidirectional"))
    )
    (net (code "69") (name "unconnected-(K2-D--PadA2)") (class "Default")
      (node (ref "K2") (pin "A2") (pinfunction "D-_A2") (pintype "bidirectional"))
    )
    (net (code "70") (name "unconnected-(K2-D--PadB2)") (class "Default")
      (node (ref "K2") (pin "B2") (pinfunction "D-_B2") (pintype "bidirectional"))
    )
    (net (code "71") (name "unconnected-(K3-D+-PadA3)") (class "Default")
      (node (ref "K3") (pin "A3") (pinfunction "D+_A3") (pintype "bidirectional"))
    )
    (net (code "72") (name "unconnected-(K3-D+-PadB3)") (class "Default")
      (node (ref "K3") (pin "B3") (pinfunction "D+_B3") (pintype "bidirectional"))
    )
    (net (code "73") (name "unconnected-(K3-D--PadA2)") (class "Default")
      (node (ref "K3") (pin "A2") (pinfunction "D-_A2") (pintype "bidirectional"))
    )
    (net (code "74") (name "unconnected-(K3-D--PadB2)") (class "Default")
      (node (ref "K3") (pin "B2") (pinfunction "D-_B2") (pintype "bidirectional"))
    )
    (net (code "75") (name "unconnected-(U$1-CLKOUT{slash}SOF-Pad3)") (class "Default")
      (node (ref "U$1") (pin "3") (pinfunction "CLKOUT/SOF_3") (pintype "output"))
    )
    (net (code "76") (name "unconnected-(U$1-~{INT}-Pad12)") (class "Default")
      (node (ref "U$1") (pin "12") (pinfunction "~{INT}_12") (pintype "output"))
    )
    (net (code "77") (name "unconnected-(U$1-~{RX0BF}-Pad11)") (class "Default")
      (node (ref "U$1") (pin "11") (pinfunction "~{RX0BF}_11") (pintype "output"))
    )
    (net (code "78") (name "unconnected-(U$1-~{RX1BF}-Pad10)") (class "Default")
      (node (ref "U$1") (pin "10") (pinfunction "~{RX1BF}_10") (pintype "output"))
    )
    (net (code "79") (name "unconnected-(U$1-~{TX0RTS}-Pad4)") (class "Default")
      (node (ref "U$1") (pin "4") (pinfunction "~{TX0RTS}_4") (pintype "input"))
    )
    (net (code "80") (name "unconnected-(U$1-~{TX1RTS}-Pad5)") (class "Default")
      (node (ref "U$1") (pin "5") (pinfunction "~{TX1RTS}_5") (pintype "input"))
    )
    (net (code "81") (name "unconnected-(U$1-~{TX2RTS}-Pad6)") (class "Default")
      (node (ref "U$1") (pin "6") (pinfunction "~{TX2RTS}_6") (pintype "input"))
    )
    (net (code "82") (name "unconnected-(U$2-RAW-Pad24)") (class "Default")
      (node (ref "U$2") (pin "24") (pinfunction "RAW_24") (pintype "bidirectional"))
    )
    (net (code "83") (name "unconnected-(U$2-RST-Pad22)") (class "Default")
      (node (ref "U$2") (pin "22") (pinfunction "RST_22") (pintype "bidirectional"))
    )
  )
)
